# Liquid_Tube.net
KiCad netlist of a schematic drawn in Altium Designer
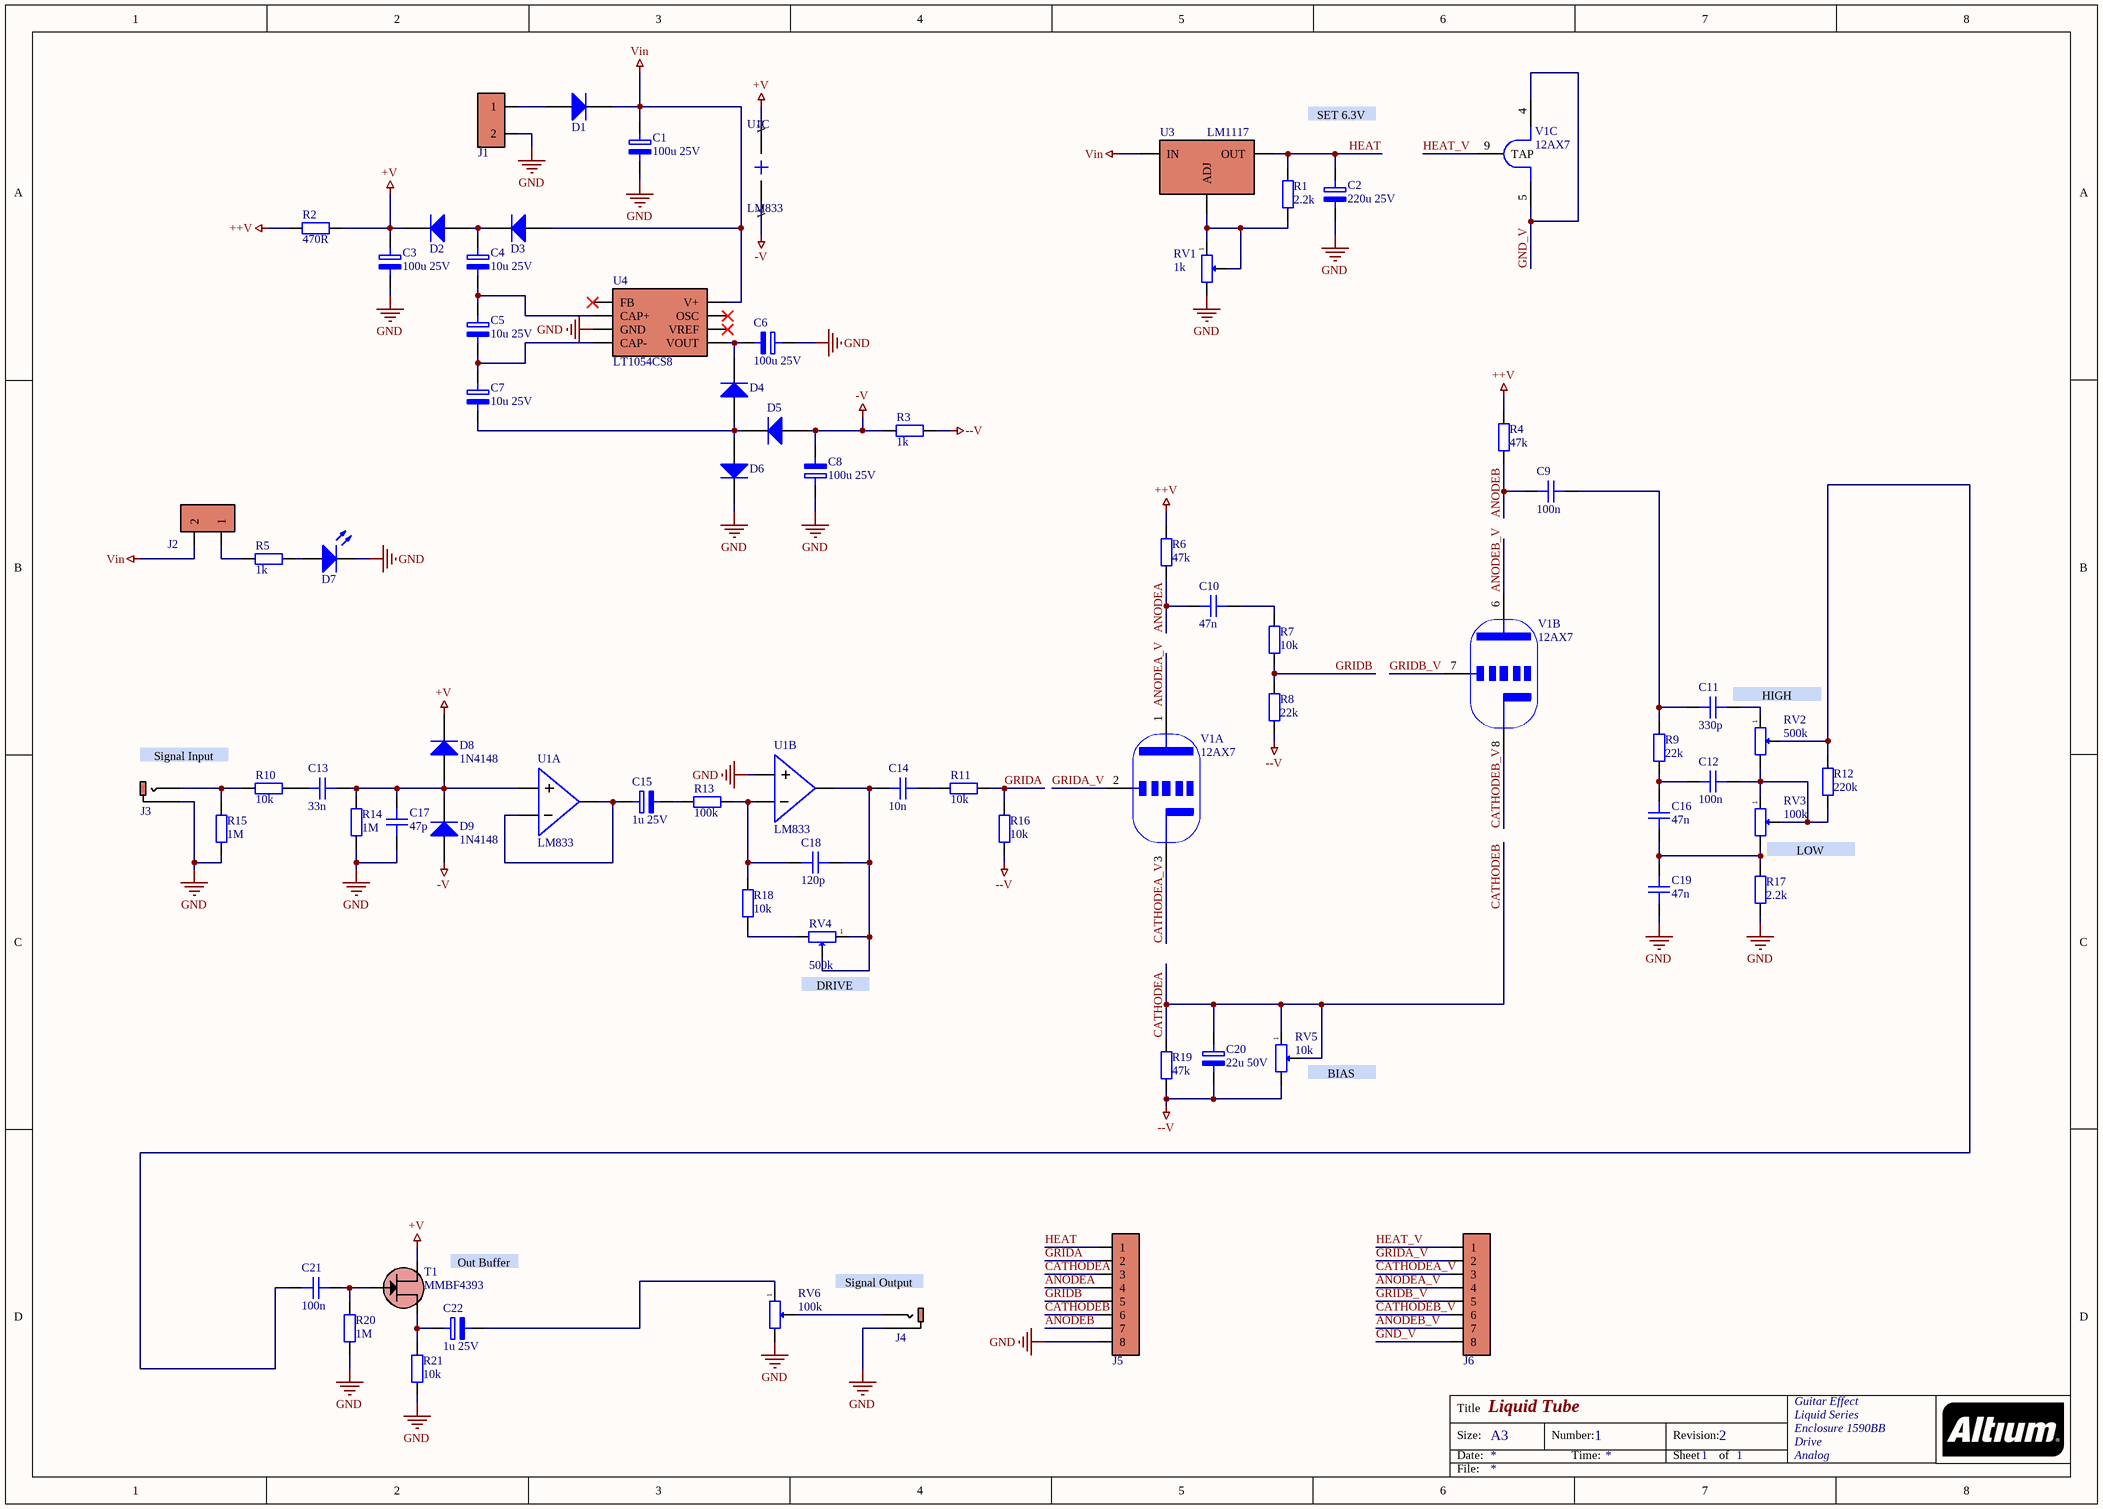
[diagram p0: Liquid Tube.SchDoc]

(export (version "E")
  (design (tool "Eeschema 10.0.6"))
  (components
    (comp (ref "C1")
      (value "100u 25V")
      (footprint "Footprints:CAPACITOR THT 6.3X11MM")
      (libsource (lib "Symbols") (part "Capacitor ALU THT 100u 25V"))
    )
    (comp (ref "C2")
      (value "220u 25V")
      (footprint "Footprints:CAPACITOR THT 6.3X11MM")
      (libsource (lib "Symbols") (part "Capacitor ALU THT 220u 25V"))
    )
    (comp (ref "C3")
      (value "100u 25V")
      (footprint "Footprints:CAPACITOR THT 6.3X11MM")
      (libsource (lib "Symbols") (part "Capacitor ALU THT 100u 25V"))
    )
    (comp (ref "C4")
      (value "10u 25V")
      (footprint "Footprints:CAPACITOR THT 5X11MM")
      (libsource (lib "Symbols") (part "Capacitor ALU THT 10u 25V"))
    )
    (comp (ref "C5")
      (value "10u 25V")
      (footprint "Footprints:CAPACITOR THT 5X11MM")
      (libsource (lib "Symbols") (part "Capacitor ALU THT 10u 25V"))
    )
    (comp (ref "C6")
      (value "100u 25V")
      (footprint "Footprints:CAPACITOR THT 6.3X11MM")
      (libsource (lib "Symbols") (part "Capacitor ALU THT 100u 25V"))
    )
    (comp (ref "C7")
      (value "10u 25V")
      (footprint "Footprints:CAPACITOR THT 5X11MM")
      (libsource (lib "Symbols") (part "Capacitor ALU THT 10u 25V"))
    )
    (comp (ref "C8")
      (value "100u 25V")
      (footprint "Footprints:CAPACITOR THT 6.3X11MM")
      (libsource (lib "Symbols") (part "Capacitor ALU THT 100u 25V"))
    )
    (comp (ref "C9")
      (value "100n")
      (footprint "Footprints:CAPACITOR 7.2X2.5MM LS=5MM MKT")
      (libsource (lib "Symbols") (part "Capacitor MKT 100n 100V"))
    )
    (comp (ref "C10")
      (value "47n")
      (footprint "Footprints:CAPACITOR 7.2X2.5MM LS=5MM MKT")
      (libsource (lib "Symbols") (part "Capacitor MKT 47n 100V"))
    )
    (comp (ref "C11")
      (value "330p")
      (footprint "Footprints:Capacitor 0603")
      (libsource (lib "Symbols") (part "Capacitor 0603 330p"))
    )
    (comp (ref "C12")
      (value "100n")
      (footprint "Footprints:CAPACITOR 7.2X2.5MM LS=5MM MKT")
      (libsource (lib "Symbols") (part "Capacitor MKT 100n 100V"))
    )
    (comp (ref "C13")
      (value "33n")
      (footprint "Footprints:CAPACITOR 7.2X2.5MM LS=5MM MKT")
      (libsource (lib "Symbols") (part "Capacitor MKT 33n 100V"))
    )
    (comp (ref "C14")
      (value "10n")
      (footprint "Footprints:CAPACITOR 7.2X2.5MM LS=5MM MKT")
      (libsource (lib "Symbols") (part "Capacitor MKT 10n 100V"))
    )
    (comp (ref "C15")
      (value "1u 25V")
      (footprint "Footprints:CAPACITOR THT 5X11MM")
      (libsource (lib "Symbols") (part "Capacitor ALU THT 1u 25V"))
    )
    (comp (ref "C16")
      (value "47n")
      (footprint "Footprints:CAPACITOR 7.2X2.5MM LS=5MM MKT")
      (libsource (lib "Symbols") (part "Capacitor MKT 47n 100V"))
    )
    (comp (ref "C17")
      (value "47p")
      (footprint "Footprints:Capacitor 0603")
      (libsource (lib "Symbols") (part "Capacitor 0603 47p"))
    )
    (comp (ref "C18")
      (value "120p")
      (footprint "Footprints:Capacitor 0603")
      (libsource (lib "Symbols") (part "Capacitor 0603 120p"))
    )
    (comp (ref "C19")
      (value "47n")
      (footprint "Footprints:CAPACITOR 7.2X2.5MM LS=5MM MKT")
      (libsource (lib "Symbols") (part "Capacitor MKT 47n 100V"))
    )
    (comp (ref "C20")
      (value "22u 50V")
      (footprint "Footprints:CAPACITOR THT 5X11MM")
      (libsource (lib "Symbols") (part "Capacitor ALU THT 22u 50V"))
    )
    (comp (ref "C21")
      (value "100n")
      (footprint "Footprints:CAPACITOR 7.2X2.5MM LS=5MM MKT")
      (libsource (lib "Symbols") (part "Capacitor MKT 100n 100V"))
    )
    (comp (ref "C22")
      (value "1u 25V")
      (footprint "Footprints:CAPACITOR THT 5X11MM")
      (libsource (lib "Symbols") (part "Capacitor ALU THT 1u 25V"))
    )
    (comp (ref "D1")
      (value "S1M-13-F")
      (footprint "Footprints:DO-214")
      (libsource (lib "Symbols") (part "Diode 1KV 1A S1M-13-F"))
    )
    (comp (ref "D2")
      (value "S1M-13-F")
      (footprint "Footprints:DO-214")
      (libsource (lib "Symbols") (part "Diode 1KV 1A S1M-13-F"))
    )
    (comp (ref "D3")
      (value "S1M-13-F")
      (footprint "Footprints:DO-214")
      (libsource (lib "Symbols") (part "Diode 1KV 1A S1M-13-F"))
    )
    (comp (ref "D4")
      (value "S1M-13-F")
      (footprint "Footprints:DO-214")
      (libsource (lib "Symbols") (part "Diode 1KV 1A S1M-13-F"))
    )
    (comp (ref "D5")
      (value "S1M-13-F")
      (footprint "Footprints:DO-214")
      (libsource (lib "Symbols") (part "Diode 1KV 1A S1M-13-F"))
    )
    (comp (ref "D6")
      (value "S1M-13-F")
      (footprint "Footprints:DO-214")
      (libsource (lib "Symbols") (part "Diode 1KV 1A S1M-13-F"))
    )
    (comp (ref "D7")
      (value "Diode LED 5mm")
      (footprint "Footprints:LED 5MM THT")
      (libsource (lib "Symbols") (part "Diode LED 5mm"))
    )
    (comp (ref "D8")
      (value "1N4148")
      (footprint "Footprints:SOD80")
      (libsource (lib "Symbols") (part "Diode SMD 1N4148 SOD80"))
    )
    (comp (ref "D9")
      (value "1N4148")
      (footprint "Footprints:SOD80")
      (libsource (lib "Symbols") (part "Diode SMD 1N4148 SOD80"))
    )
    (comp (ref "J1")
      (value "Mechanical Goldpin 1x2 THT 2.54mm")
      (footprint "Footprints:GOLDPIN 1X2")
      (libsource (lib "") (part "Mechanical Goldpin 1x2 THT 2.54mm_1"))
    )
    (comp (ref "J2")
      (value "Mechanical Goldpin 1x2 THT 2.54mm")
      (footprint "Footprints:GOLDPIN 1X2")
      (libsource (lib "Symbols") (part "Mechanical Goldpin 1x2 THT 2.54mm"))
    )
    (comp (ref "J3")
      (value "ACJM-MVS")
      (footprint "Footprints:MECHANICAL JACK MONO ACJM-MVS")
      (libsource (lib "Symbols") (part "Mechanical JACK Panel Mono Female Amphenol ACJM-MVS"))
    )
    (comp (ref "J4")
      (value "ACJM-MVS")
      (footprint "Footprints:MECHANICAL JACK MONO ACJM-MVS")
      (libsource (lib "") (part "Mechanical JACK Panel Mono Female Amphenol ACJM-MVS_1"))
    )
    (comp (ref "J5")
      (value "Mechanical Goldpin 1x8 THT 2.54mm")
      (footprint "Footprints:GOLDPIN 1X8")
      (libsource (lib "Symbols") (part "Mechanical Goldpin 1x8 THT 2.54mm"))
    )
    (comp (ref "J6")
      (value "Mechanical Goldpin 1x8 THT 2.54mm")
      (footprint "Footprints:GOLDPIN 1X8")
      (libsource (lib "Symbols") (part "Mechanical Goldpin 1x8 THT 2.54mm"))
    )
    (comp (ref "R1")
      (value "2.2k")
      (footprint "Footprints:Resistor 0603")
      (libsource (lib "Symbols") (part "Resistor 0603 2.2k"))
    )
    (comp (ref "R2")
      (value "470R")
      (footprint "Footprints:Resistor 0603")
      (libsource (lib "Symbols") (part "Resistor 0603 470R"))
    )
    (comp (ref "R3")
      (value "1k")
      (footprint "Footprints:Resistor 0603")
      (libsource (lib "Symbols") (part "Resistor 0603 1k"))
    )
    (comp (ref "R4")
      (value "47k")
      (footprint "Footprints:Resistor 0603")
      (libsource (lib "Symbols") (part "Resistor 0603 47k"))
    )
    (comp (ref "R5")
      (value "1k")
      (footprint "Footprints:Resistor 0603")
      (libsource (lib "Symbols") (part "Resistor 0603 1k"))
    )
    (comp (ref "R6")
      (value "47k")
      (footprint "Footprints:Resistor 0603")
      (libsource (lib "Symbols") (part "Resistor 0603 47k"))
    )
    (comp (ref "R7")
      (value "10k")
      (footprint "Footprints:Resistor 0603")
      (libsource (lib "Symbols") (part "Resistor 0603 10k"))
    )
    (comp (ref "R8")
      (value "22k")
      (footprint "Footprints:Resistor 0603")
      (libsource (lib "Symbols") (part "Resistor 0603 22k"))
    )
    (comp (ref "R9")
      (value "22k")
      (footprint "Footprints:Resistor 0603")
      (libsource (lib "Symbols") (part "Resistor 0603 22k"))
    )
    (comp (ref "R10")
      (value "10k")
      (footprint "Footprints:Resistor 0603")
      (libsource (lib "") (part "Resistor 0603 10k_2"))
    )
    (comp (ref "R11")
      (value "10k")
      (footprint "Footprints:Resistor 0603")
      (libsource (lib "") (part "Resistor 0603 10k_1"))
    )
    (comp (ref "R12")
      (value "220k")
      (footprint "Footprints:Resistor 0603")
      (libsource (lib "Symbols") (part "Resistor 0603 220k"))
    )
    (comp (ref "R13")
      (value "100k")
      (footprint "Footprints:Resistor 0603")
      (libsource (lib "Symbols") (part "Resistor 0603 100k"))
    )
    (comp (ref "R14")
      (value "1M")
      (footprint "Footprints:Resistor 0603")
      (libsource (lib "Symbols") (part "Resistor 0603 1Meg"))
    )
    (comp (ref "R15")
      (value "1M")
      (footprint "Footprints:Resistor 0603")
      (libsource (lib "Symbols") (part "Resistor 0603 1Meg"))
    )
    (comp (ref "R16")
      (value "10k")
      (footprint "Footprints:Resistor 0603")
      (libsource (lib "") (part "Resistor 0603 10k_3"))
    )
    (comp (ref "R17")
      (value "2.2k")
      (footprint "Footprints:Resistor 0603")
      (libsource (lib "Symbols") (part "Resistor 0603 2.2k"))
    )
    (comp (ref "R18")
      (value "10k")
      (footprint "Footprints:Resistor 0603")
      (libsource (lib "Symbols") (part "Resistor 0603 10k"))
    )
    (comp (ref "R19")
      (value "47k")
      (footprint "Footprints:Resistor 0603")
      (libsource (lib "Symbols") (part "Resistor 0603 47k"))
    )
    (comp (ref "R20")
      (value "1M")
      (footprint "Footprints:Resistor 0603")
      (libsource (lib "Symbols") (part "Resistor 0603 1Meg"))
    )
    (comp (ref "R21")
      (value "10k")
      (footprint "Footprints:Resistor 0603")
      (libsource (lib "Symbols") (part "Resistor 0603 10k"))
    )
    (comp (ref "RV1")
      (value "1k")
      (footprint "Footprints:POTENTIOMETER 1.2X3.8MM")
      (libsource (lib "Symbols") (part "Potentiometer SMD 1.2x3.8mm 1k"))
    )
    (comp (ref "RV2")
      (value "500k")
      (footprint "Footprints:POTENTIOMETER 9x11mm ALPS-RK097 THT")
      (libsource (lib "") (part "Potentiometer 9x11mm Panel 500k MONO LIN ALPS-RK097_1"))
    )
    (comp (ref "RV3")
      (value "100k")
      (footprint "Footprints:POTENTIOMETER 9x11mm ALPS-RK097 THT")
      (libsource (lib "Symbols") (part "Potentiometer 9x11mm Panel 100k MONO LIN ALPS-RK097"))
    )
    (comp (ref "RV4")
      (value "500k")
      (footprint "Footprints:POTENTIOMETER 9x11mm ALPS-RK097 THT")
      (libsource (lib "Symbols") (part "Potentiometer 9x11mm Panel 500k MONO LIN ALPS-RK097"))
    )
    (comp (ref "RV5")
      (value "10k")
      (footprint "Footprints:POTENTIOMETER 9x11mm ALPS-RK097 THT")
      (libsource (lib "Symbols") (part "Potentiometer 9x11mm Panel 10k MONO LIN ALPS-RK097"))
    )
    (comp (ref "RV6")
      (value "100k")
      (footprint "Footprints:POTENTIOMETER 9x11mm ALPS-RK097 THT")
      (libsource (lib "Symbols") (part "Potentiometer 9x11mm Panel 100k MONO LIN ALPS-RK097"))
    )
    (comp (ref "T1")
      (value "MMBF4393")
      (footprint "Footprints:SOT23-3")
      (libsource (lib "Symbols") (part "Transistor N-JFET SMD SOT23 MMBF4393"))
    )
    (comp (ref "U1")
      (value "LM833")
      (footprint "Footprints:SO8")
      (libsource (lib "Symbols") (part "IC OP-AMP LM833 SO8"))
    )
    (comp (ref "U3")
      (value "LM1117")
      (footprint "Footprints:TO252")
      (libsource (lib "Symbols") (part "IC LM1117 LDO TO252 ADJ"))
    )
    (comp (ref "U4")
      (value "LT1054CS8")
      (footprint "Footprints:SO8")
      (libsource (lib "Symbols") (part "IC 100mA Sw Cap SO8 LT1054CS8"))
    )
    (comp (ref "V1")
      (value "12AX7")
      (footprint "Footprints:TUbe 9pin NOVAL")
      (libsource (lib "Symbols") (part "Tube 12AX7 / ECC83 9pin NOVAL"))
    )
  )
  (nets
    (net (code "1") (name "++V") (class "Default")
      (node (ref "R2") (pin "1") (pinfunction "1_1") (pintype "passive"))
      (node (ref "R4") (pin "2") (pinfunction "2_2") (pintype "passive"))
      (node (ref "R6") (pin "2") (pinfunction "2_2") (pintype "passive"))
    )
    (net (code "2") (name "+V") (class "Default")
      (node (ref "C3") (pin "1") (pinfunction "1_1") (pintype "passive"))
      (node (ref "D2") (pin "2") (pinfunction "2_2") (pintype "passive"))
      (node (ref "D8") (pin "2") (pinfunction "2_2") (pintype "passive"))
      (node (ref "R2") (pin "2") (pinfunction "2_2") (pintype "passive"))
      (node (ref "T1") (pin "1") (pinfunction "D_1") (pintype "passive"))
      (node (ref "U1") (pin "8") (pinfunction "V+_8") (pintype "passive"))
    )
    (net (code "3") (name "--V") (class "Default")
      (node (ref "C20") (pin "2") (pinfunction "2_2") (pintype "passive"))
      (node (ref "R16") (pin "2") (pinfunction "2_2") (pintype "passive"))
      (node (ref "R19") (pin "1") (pinfunction "1_1") (pintype "passive"))
      (node (ref "R3") (pin "2") (pinfunction "2_2") (pintype "passive"))
      (node (ref "R8") (pin "1") (pinfunction "1_1") (pintype "passive"))
      (node (ref "RV5") (pin "3") (pinfunction "3_3") (pintype "passive"))
    )
    (net (code "4") (name "-V") (class "Default")
      (node (ref "C8") (pin "2") (pinfunction "2_2") (pintype "passive"))
      (node (ref "D5") (pin "1") (pinfunction "1_1") (pintype "passive"))
      (node (ref "D9") (pin "1") (pinfunction "1_1") (pintype "passive"))
      (node (ref "R3") (pin "1") (pinfunction "1_1") (pintype "passive"))
      (node (ref "U1") (pin "4") (pinfunction "V-_4") (pintype "passive"))
    )
    (net (code "5") (name "/ANODEA") (class "Default")
      (node (ref "C10") (pin "1") (pinfunction "1_1") (pintype "passive"))
      (node (ref "J5") (pin "4") (pinfunction "4_4") (pintype "passive"))
      (node (ref "R6") (pin "1") (pinfunction "1_1") (pintype "passive"))
    )
    (net (code "6") (name "/ANODEA_V") (class "Default")
      (node (ref "J6") (pin "4") (pinfunction "4_4") (pintype "passive"))
      (node (ref "V1") (pin "1") (pinfunction "PLATE2_1") (pintype "passive"))
    )
    (net (code "7") (name "/ANODEB") (class "Default")
      (node (ref "C9") (pin "1") (pinfunction "1_1") (pintype "passive"))
      (node (ref "J5") (pin "7") (pinfunction "7_7") (pintype "passive"))
      (node (ref "R4") (pin "1") (pinfunction "1_1") (pintype "passive"))
    )
    (net (code "8") (name "/ANODEB_V") (class "Default")
      (node (ref "J6") (pin "7") (pinfunction "7_7") (pintype "passive"))
      (node (ref "V1") (pin "6") (pinfunction "PLATE1_6") (pintype "passive"))
    )
    (net (code "9") (name "/CATHODEA") (class "Default")
      (node (ref "C20") (pin "1") (pinfunction "1_1") (pintype "passive"))
      (node (ref "J5") (pin "3") (pinfunction "3_3") (pintype "passive"))
      (node (ref "J5") (pin "6") (pinfunction "6_6") (pintype "passive"))
      (node (ref "R19") (pin "2") (pinfunction "2_2") (pintype "passive"))
      (node (ref "RV5") (pin "1") (pinfunction "1_1") (pintype "passive"))
      (node (ref "RV5") (pin "2") (pinfunction "2_2") (pintype "passive"))
    )
    (net (code "10") (name "/CATHODEA_V") (class "Default")
      (node (ref "J6") (pin "3") (pinfunction "3_3") (pintype "passive"))
      (node (ref "V1") (pin "3") (pinfunction "CATHODE2_3") (pintype "passive"))
    )
    (net (code "11") (name "/CATHODEB_V") (class "Default")
      (node (ref "J6") (pin "6") (pinfunction "6_6") (pintype "passive"))
      (node (ref "V1") (pin "8") (pinfunction "CATHODE1_8") (pintype "passive"))
    )
    (net (code "12") (name "/GND_V") (class "Default")
      (node (ref "J6") (pin "8") (pinfunction "8_8") (pintype "passive"))
      (node (ref "V1") (pin "4") (pinfunction "FIL1_4") (pintype "passive"))
      (node (ref "V1") (pin "5") (pinfunction "FIL2_5") (pintype "passive"))
    )
    (net (code "13") (name "/GRIDA") (class "Default")
      (node (ref "J5") (pin "2") (pinfunction "2_2") (pintype "passive"))
      (node (ref "R11") (pin "1") (pinfunction "1_1") (pintype "passive"))
      (node (ref "R16") (pin "1") (pinfunction "1_1") (pintype "passive"))
    )
    (net (code "14") (name "/GRIDA_V") (class "Default")
      (node (ref "J6") (pin "2") (pinfunction "2_2") (pintype "passive"))
      (node (ref "V1") (pin "2") (pinfunction "GRID2_2") (pintype "passive"))
    )
    (net (code "15") (name "/GRIDB") (class "Default")
      (node (ref "J5") (pin "5") (pinfunction "5_5") (pintype "passive"))
      (node (ref "R7") (pin "1") (pinfunction "1_1") (pintype "passive"))
      (node (ref "R8") (pin "2") (pinfunction "2_2") (pintype "passive"))
    )
    (net (code "16") (name "/GRIDB_V") (class "Default")
      (node (ref "J6") (pin "5") (pinfunction "5_5") (pintype "passive"))
      (node (ref "V1") (pin "7") (pinfunction "GRID1_7") (pintype "passive"))
    )
    (net (code "17") (name "/HEAT") (class "Default")
      (node (ref "C2") (pin "1") (pinfunction "1_1") (pintype "passive"))
      (node (ref "J5") (pin "1") (pinfunction "1_1") (pintype "passive"))
      (node (ref "R1") (pin "2") (pinfunction "2_2") (pintype "passive"))
      (node (ref "U3") (pin "2") (pinfunction "OUT_2") (pintype "passive"))
    )
    (net (code "18") (name "/HEAT_V") (class "Default")
      (node (ref "J6") (pin "1") (pinfunction "1_1") (pintype "passive"))
      (node (ref "V1") (pin "9") (pinfunction "TAP_9") (pintype "passive"))
    )
    (net (code "19") (name "GND") (class "Default")
      (node (ref "C1") (pin "2") (pinfunction "2_2") (pintype "passive"))
      (node (ref "C17") (pin "1") (pinfunction "1_1") (pintype "passive"))
      (node (ref "C19") (pin "1") (pinfunction "1_1") (pintype "passive"))
      (node (ref "C2") (pin "2") (pinfunction "2_2") (pintype "passive"))
      (node (ref "C3") (pin "2") (pinfunction "2_2") (pintype "passive"))
      (node (ref "C6") (pin "1") (pinfunction "1_1") (pintype "passive"))
      (node (ref "C8") (pin "1") (pinfunction "1_1") (pintype "passive"))
      (node (ref "D6") (pin "2") (pinfunction "2_2") (pintype "passive"))
      (node (ref "D7") (pin "2") (pinfunction "2_2") (pintype "passive"))
      (node (ref "J1") (pin "2") (pinfunction "2_2") (pintype "passive"))
      (node (ref "J3") (pin "2") (pinfunction "2_2") (pintype "passive"))
      (node (ref "J4") (pin "2") (pinfunction "2_2") (pintype "passive"))
      (node (ref "J5") (pin "8") (pinfunction "8_8") (pintype "passive"))
      (node (ref "R14") (pin "1") (pinfunction "1_1") (pintype "passive"))
      (node (ref "R15") (pin "1") (pinfunction "1_1") (pintype "passive"))
      (node (ref "R17") (pin "1") (pinfunction "1_1") (pintype "passive"))
      (node (ref "R20") (pin "1") (pinfunction "1_1") (pintype "passive"))
      (node (ref "R21") (pin "1") (pinfunction "1_1") (pintype "passive"))
      (node (ref "RV1") (pin "3") (pinfunction "3_3") (pintype "passive"))
      (node (ref "RV6") (pin "3") (pinfunction "3_3") (pintype "passive"))
      (node (ref "U1") (pin "5") (pinfunction "IN+_5") (pintype "passive"))
      (node (ref "U4") (pin "3") (pinfunction "GND_3") (pintype "passive"))
    )
    (net (code "20") (name "Net-(C4-Pad1)") (class "Default")
      (node (ref "C4") (pin "1") (pinfunction "1_1") (pintype "passive"))
      (node (ref "D2") (pin "1") (pinfunction "1_1") (pintype "passive"))
      (node (ref "D3") (pin "2") (pinfunction "2_2") (pintype "passive"))
    )
    (net (code "21") (name "Net-(C7-Pad2)") (class "Default")
      (node (ref "C7") (pin "2") (pinfunction "2_2") (pintype "passive"))
      (node (ref "D4") (pin "1") (pinfunction "1_1") (pintype "passive"))
      (node (ref "D5") (pin "2") (pinfunction "2_2") (pintype "passive"))
      (node (ref "D6") (pin "1") (pinfunction "1_1") (pintype "passive"))
    )
    (net (code "22") (name "Net-(C10-Pad2)") (class "Default")
      (node (ref "C10") (pin "2") (pinfunction "2_2") (pintype "passive"))
      (node (ref "R7") (pin "2") (pinfunction "2_2") (pintype "passive"))
    )
    (net (code "23") (name "Net-(C11-Pad1)") (class "Default")
      (node (ref "C11") (pin "1") (pinfunction "1_1") (pintype "passive"))
      (node (ref "C9") (pin "2") (pinfunction "2_2") (pintype "passive"))
      (node (ref "R9") (pin "2") (pinfunction "2_2") (pintype "passive"))
    )
    (net (code "24") (name "Net-(C11-Pad2)") (class "Default")
      (node (ref "C11") (pin "2") (pinfunction "2_2") (pintype "passive"))
      (node (ref "RV2") (pin "1") (pinfunction "1_1") (pintype "passive"))
    )
    (net (code "25") (name "Net-(C12-Pad1)") (class "Default")
      (node (ref "C12") (pin "1") (pinfunction "1_1") (pintype "passive"))
      (node (ref "C16") (pin "2") (pinfunction "2_2") (pintype "passive"))
      (node (ref "R9") (pin "1") (pinfunction "1_1") (pintype "passive"))
    )
    (net (code "26") (name "Net-(C12-Pad2)") (class "Default")
      (node (ref "C12") (pin "2") (pinfunction "2_2") (pintype "passive"))
      (node (ref "R12") (pin "1") (pinfunction "1_1") (pintype "passive"))
      (node (ref "RV2") (pin "3") (pinfunction "3_3") (pintype "passive"))
      (node (ref "RV3") (pin "1") (pinfunction "1_1") (pintype "passive"))
      (node (ref "RV3") (pin "2") (pinfunction "2_2") (pintype "passive"))
    )
    (net (code "27") (name "Net-(C13-Pad1)") (class "Default")
      (node (ref "C13") (pin "1") (pinfunction "1_1") (pintype "passive"))
      (node (ref "R10") (pin "2") (pinfunction "2_2") (pintype "passive"))
    )
    (net (code "28") (name "Net-(C14-Pad2)") (class "Default")
      (node (ref "C14") (pin "2") (pinfunction "2_2") (pintype "passive"))
      (node (ref "R11") (pin "2") (pinfunction "2_2") (pintype "passive"))
    )
    (net (code "29") (name "Net-(C15-Pad2)") (class "Default")
      (node (ref "C15") (pin "2") (pinfunction "2_2") (pintype "passive"))
      (node (ref "R13") (pin "1") (pinfunction "1_1") (pintype "passive"))
    )
    (net (code "30") (name "Net-(C16-Pad1)") (class "Default")
      (node (ref "C16") (pin "1") (pinfunction "1_1") (pintype "passive"))
      (node (ref "C19") (pin "2") (pinfunction "2_2") (pintype "passive"))
      (node (ref "R17") (pin "2") (pinfunction "2_2") (pintype "passive"))
      (node (ref "RV3") (pin "3") (pinfunction "3_3") (pintype "passive"))
    )
    (net (code "31") (name "Net-(C21-Pad1)") (class "Default")
      (node (ref "C21") (pin "1") (pinfunction "1_1") (pintype "passive"))
      (node (ref "R12") (pin "2") (pinfunction "2_2") (pintype "passive"))
      (node (ref "RV2") (pin "2") (pinfunction "2_2") (pintype "passive"))
    )
    (net (code "32") (name "Net-(C22-Pad2)") (class "Default")
      (node (ref "C22") (pin "2") (pinfunction "2_2") (pintype "passive"))
      (node (ref "RV6") (pin "1") (pinfunction "1_1") (pintype "passive"))
    )
    (net (code "33") (name "Net-(D1-Pad1)") (class "Default")
      (node (ref "D1") (pin "1") (pinfunction "1_1") (pintype "passive"))
      (node (ref "J1") (pin "1") (pinfunction "1_1") (pintype "passive"))
    )
    (net (code "34") (name "Net-(D7-Pad1)") (class "Default")
      (node (ref "D7") (pin "1") (pinfunction "1_1") (pintype "passive"))
      (node (ref "R5") (pin "2") (pinfunction "2_2") (pintype "passive"))
    )
    (net (code "35") (name "Net-(J2-Pad1)") (class "Default")
      (node (ref "J2") (pin "1") (pinfunction "1_1") (pintype "passive"))
      (node (ref "R5") (pin "1") (pinfunction "1_1") (pintype "passive"))
    )
    (net (code "36") (name "Net-(J3-Pad1)") (class "Default")
      (node (ref "J3") (pin "1") (pinfunction "1_1") (pintype "passive"))
      (node (ref "R10") (pin "1") (pinfunction "1_1") (pintype "passive"))
      (node (ref "R15") (pin "2") (pinfunction "2_2") (pintype "passive"))
    )
    (net (code "37") (name "Net-(J4-Pad1)") (class "Default")
      (node (ref "J4") (pin "1") (pinfunction "1_1") (pintype "passive"))
      (node (ref "RV6") (pin "2") (pinfunction "2_2") (pintype "passive"))
    )
    (net (code "38") (name "Net-(R18-Pad1)") (class "Default")
      (node (ref "R18") (pin "1") (pinfunction "1_1") (pintype "passive"))
      (node (ref "RV4") (pin "3") (pinfunction "3_3") (pintype "passive"))
    )
    (net (code "39") (name "Net-(T1-G)") (class "Default")
      (node (ref "C21") (pin "2") (pinfunction "2_2") (pintype "passive"))
      (node (ref "R20") (pin "2") (pinfunction "2_2") (pintype "passive"))
      (node (ref "T1") (pin "3") (pinfunction "G_3") (pintype "passive"))
    )
    (net (code "40") (name "Net-(T1-S)") (class "Default")
      (node (ref "C22") (pin "1") (pinfunction "1_1") (pintype "passive"))
      (node (ref "R21") (pin "2") (pinfunction "2_2") (pintype "passive"))
      (node (ref "T1") (pin "2") (pinfunction "S_2") (pintype "passive"))
    )
    (net (code "41") (name "Net-(U1A-IN+)") (class "Default")
      (node (ref "C13") (pin "2") (pinfunction "2_2") (pintype "passive"))
      (node (ref "C17") (pin "2") (pinfunction "2_2") (pintype "passive"))
      (node (ref "D8") (pin "1") (pinfunction "1_1") (pintype "passive"))
      (node (ref "D9") (pin "2") (pinfunction "2_2") (pintype "passive"))
      (node (ref "R14") (pin "2") (pinfunction "2_2") (pintype "passive"))
      (node (ref "U1") (pin "3") (pinfunction "IN+_3") (pintype "passive"))
    )
    (net (code "42") (name "Net-(U1A-IN-)") (class "Default")
      (node (ref "C15") (pin "1") (pinfunction "1_1") (pintype "passive"))
      (node (ref "U1") (pin "1") (pinfunction "OUT_1") (pintype "passive"))
      (node (ref "U1") (pin "2") (pinfunction "IN-_2") (pintype "passive"))
    )
    (net (code "43") (name "Net-(U1B-IN-)") (class "Default")
      (node (ref "C18") (pin "1") (pinfunction "1_1") (pintype "passive"))
      (node (ref "R13") (pin "2") (pinfunction "2_2") (pintype "passive"))
      (node (ref "R18") (pin "2") (pinfunction "2_2") (pintype "passive"))
      (node (ref "U1") (pin "6") (pinfunction "IN-_6") (pintype "passive"))
    )
    (net (code "44") (name "Net-(U1B-OUT)") (class "Default")
      (node (ref "C14") (pin "1") (pinfunction "1_1") (pintype "passive"))
      (node (ref "C18") (pin "2") (pinfunction "2_2") (pintype "passive"))
      (node (ref "RV4") (pin "1") (pinfunction "1_1") (pintype "passive"))
      (node (ref "RV4") (pin "2") (pinfunction "2_2") (pintype "passive"))
      (node (ref "U1") (pin "7") (pinfunction "OUT_7") (pintype "passive"))
    )
    (net (code "45") (name "Net-(U3-ADJ)") (class "Default")
      (node (ref "R1") (pin "1") (pinfunction "1_1") (pintype "passive"))
      (node (ref "RV1") (pin "1") (pinfunction "1_1") (pintype "passive"))
      (node (ref "RV1") (pin "2") (pinfunction "2_2") (pintype "passive"))
      (node (ref "U3") (pin "1") (pinfunction "ADJ_1") (pintype "passive"))
    )
    (net (code "46") (name "Net-(U4-CAP+)") (class "Default")
      (node (ref "C4") (pin "2") (pinfunction "2_2") (pintype "passive"))
      (node (ref "C5") (pin "1") (pinfunction "1_1") (pintype "passive"))
      (node (ref "U4") (pin "2") (pinfunction "CAP+_2") (pintype "passive"))
    )
    (net (code "47") (name "Net-(U4-CAP-)") (class "Default")
      (node (ref "C5") (pin "2") (pinfunction "2_2") (pintype "passive"))
      (node (ref "C7") (pin "1") (pinfunction "1_1") (pintype "passive"))
      (node (ref "U4") (pin "4") (pinfunction "CAP-_4") (pintype "passive"))
    )
    (net (code "48") (name "Net-(U4-VOUT)") (class "Default")
      (node (ref "C6") (pin "2") (pinfunction "2_2") (pintype "passive"))
      (node (ref "D4") (pin "2") (pinfunction "2_2") (pintype "passive"))
      (node (ref "U4") (pin "5") (pinfunction "VOUT_5") (pintype "passive"))
    )
    (net (code "49") (name "Vin") (class "Default")
      (node (ref "C1") (pin "1") (pinfunction "1_1") (pintype "passive"))
      (node (ref "D1") (pin "2") (pinfunction "2_2") (pintype "passive"))
      (node (ref "D3") (pin "1") (pinfunction "1_1") (pintype "passive"))
      (node (ref "J2") (pin "2") (pinfunction "2_2") (pintype "passive"))
      (node (ref "U3") (pin "3") (pinfunction "IN_3") (pintype "passive"))
      (node (ref "U4") (pin "8") (pinfunction "V+_8") (pintype "passive"))
    )
    (net (code "50") (name "unconnected-(U4-FB-Pad1)") (class "Default")
      (node (ref "U4") (pin "1") (pinfunction "FB_1") (pintype "passive+no_connect"))
    )
    (net (code "51") (name "unconnected-(U4-OSC-Pad7)") (class "Default")
      (node (ref "U4") (pin "7") (pinfunction "OSC_7") (pintype "passive+no_connect"))
    )
    (net (code "52") (name "unconnected-(U4-VREF-Pad6)") (class "Default")
      (node (ref "U4") (pin "6") (pinfunction "VREF_6") (pintype "passive+no_connect"))
    )
  )
)
